# Supply_Power.net
KiCad netlist of a schematic drawn in Altium Designer
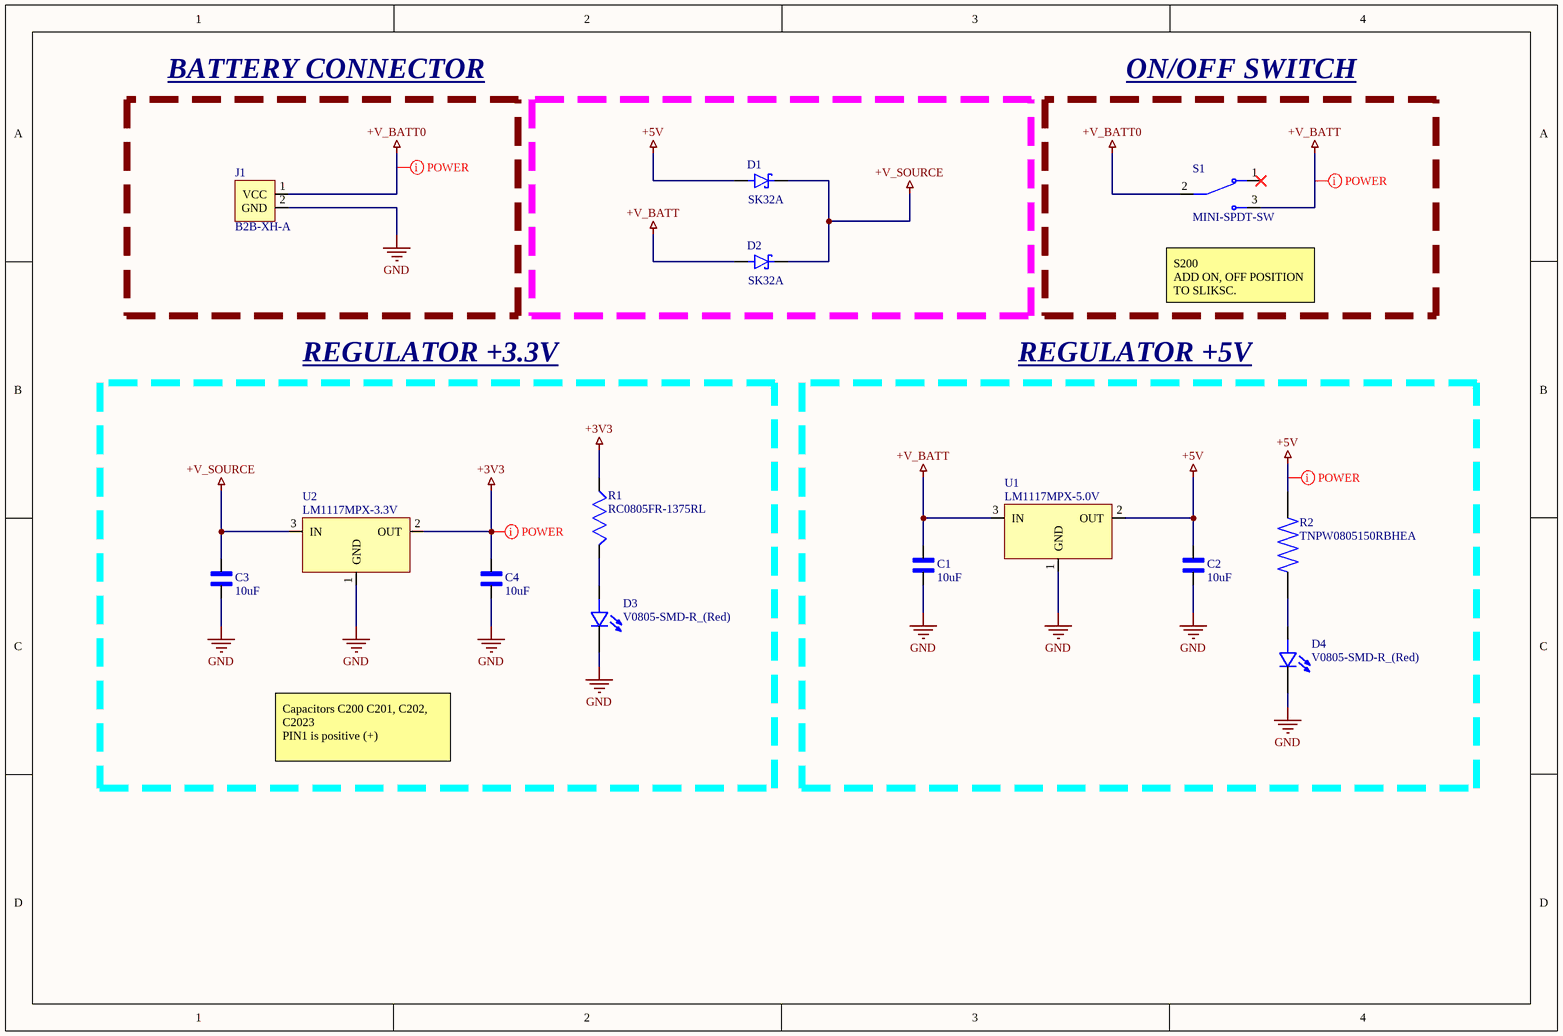
[diagram p0: Supply Power.SchDoc]

(export (version "E")
  (design (tool "Eeschema 10.0.6"))
  (components
    (comp (ref "C1")
      (value "10uF")
      (footprint "CAPPC7343X430N")
      (description "Capacitor,10uF,35VDC,10-% Tol,10+% Tol")
      (fields (field (name "MF") "{'manufacturer': u'KEMET'}") (field (name "MP") "T495D106K035AHE300"))
      (libsource (lib "Capacitor01") (part "T495D106K035AHE300"))
    )
    (comp (ref "C2")
      (value "10uF")
      (footprint "CAPPC7343X430N")
      (description "Capacitor,10uF,35VDC,10-% Tol,10+% Tol")
      (fields (field (name "MF") "{'manufacturer': u'KEMET'}") (field (name "MP") "T495D106K035AHE300"))
      (libsource (lib "Capacitor01") (part "T495D106K035AHE300"))
    )
    (comp (ref "C3")
      (value "10uF")
      (footprint "CAPPC7343X430N")
      (description "Capacitor,10uF,35VDC,10-% Tol,10+% Tol")
      (fields (field (name "MF") "{'manufacturer': u'KEMET'}") (field (name "MP") "T495D106K035AHE300"))
      (libsource (lib "Capacitor01") (part "T495D106K035AHE300"))
    )
    (comp (ref "C4")
      (value "10uF")
      (footprint "CAPPC7343X430N")
      (description "Capacitor,10uF,35VDC,10-% Tol,10+% Tol")
      (fields (field (name "MF") "{'manufacturer': u'KEMET'}") (field (name "MP") "T495D106K035AHE300"))
      (libsource (lib "Capacitor01") (part "T495D106K035AHE300"))
    )
    (comp (ref "D1")
      (value "SK32A")
      (footprint "SK32A:DIOM4325X250N")
      (fields (field (name "MF") "{'manufacturer': u'Taiwan Semiconductor'}"))
      (libsource (lib "*") (part "SK32A"))
    )
    (comp (ref "D2")
      (value "SK32A")
      (footprint "SK32A:DIOM4325X250N")
      (fields (field (name "MF") "{'manufacturer': u'Taiwan Semiconductor'}"))
      (libsource (lib "*") (part "SK32A"))
    )
    (comp (ref "D3")
      (value "V0805-SMD-R_(Red)")
      (footprint "LED_V0805-SMD-R (Red)")
      (description "V0805 - Valcon 0805 Type Surface Mount LED")
      (fields (field (name "MF") "{'manufacturer': u'Valcon'}"))
      (libsource (lib "Diode01") (part "V0805-SMD-R_(Red)"))
    )
    (comp (ref "D4")
      (value "V0805-SMD-R_(Red)")
      (footprint "LED_V0805-SMD-R (Red)")
      (description "V0805 - Valcon 0805 Type Surface Mount LED")
      (fields (field (name "MF") "{'manufacturer': u'Valcon'}"))
      (libsource (lib "Diode01") (part "V0805-SMD-R_(Red)"))
    )
    (comp (ref "J1")
      (value "B2B-XH-A")
      (footprint "B2B-XH-A")
      (libsource (lib "Sch_Library") (part "B2B-XH-A-2Pin"))
    )
    (comp (ref "R1")
      (value "RC0805FR-1375RL")
      (footprint "RESC2012X60N")
      (fields (field (name "MF") "{'manufacturer': u'Yageo'}"))
      (libsource (lib "Resistor01") (part "RC0805FR-1375RL"))
    )
    (comp (ref "R2")
      (value "TNPW0805150RBHEA")
      (footprint "RESC2012X55N")
      (fields (field (name "MF") "{'manufacturer': u'Vishay'}"))
      (libsource (lib "Resistor01") (part "TNPW0805150RBHEA"))
    )
    (comp (ref "S1")
      (value "MINI-SPDT-SW")
      (footprint "SW_MINI-SPDT-SW")
      (fields (field (name "MF") "{'manufacturer': u'Gravitech'}"))
      (libsource (lib "Button") (part "MINI-SPDT-SW"))
    )
    (comp (ref "U1")
      (value "LM1117MPX-5.0V")
      (footprint "SOT230P700X180-4N")
      (description "LM1117MPX-50NOPB")
      (libsource (lib "Sch_Library") (part "LM1117MPX-5.0V"))
    )
    (comp (ref "U2")
      (value "LM1117MPX-3.3V")
      (footprint "SOT230P700X180-4N")
      (description "LM1117MPX-33NOPB")
      (libsource (lib "Sch_Library") (part "LM1117MPX-3.3V"))
    )
  )
  (nets
    (net (code "1") (name "+3V3") (class "Default")
      (node (ref "C4") (pin "1") (pinfunction "1_1") (pintype "passive"))
      (node (ref "R1") (pin "2") (pinfunction "2_2") (pintype "passive"))
      (node (ref "U2") (pin "2") (pinfunction "OUT_2") (pintype "passive"))
    )
    (net (code "2") (name "+5V") (class "Default")
      (node (ref "C2") (pin "1") (pinfunction "1_1") (pintype "passive"))
      (node (ref "D1") (pin "A") (pinfunction "A_A") (pintype "passive"))
      (node (ref "R2") (pin "2") (pinfunction "2_2") (pintype "passive"))
      (node (ref "U1") (pin "2") (pinfunction "OUT_2") (pintype "passive"))
    )
    (net (code "3") (name "+V_BATT") (class "Default")
      (node (ref "C1") (pin "1") (pinfunction "1_1") (pintype "passive"))
      (node (ref "D2") (pin "A") (pinfunction "A_A") (pintype "passive"))
      (node (ref "S1") (pin "3") (pinfunction "3_3") (pintype "passive"))
      (node (ref "U1") (pin "3") (pinfunction "IN_3") (pintype "passive"))
    )
    (net (code "4") (name "+V_BATT0") (class "Default")
      (node (ref "J1") (pin "1") (pinfunction "VCC_1") (pintype "passive"))
      (node (ref "S1") (pin "2") (pinfunction "2_2") (pintype "passive"))
    )
    (net (code "5") (name "+V_SOURCE") (class "Default")
      (node (ref "C3") (pin "1") (pinfunction "1_1") (pintype "passive"))
      (node (ref "D1") (pin "C") (pinfunction "K_C") (pintype "passive"))
      (node (ref "D2") (pin "C") (pinfunction "K_C") (pintype "passive"))
      (node (ref "U2") (pin "3") (pinfunction "IN_3") (pintype "passive"))
    )
    (net (code "6") (name "GND") (class "Default")
      (node (ref "C1") (pin "2") (pinfunction "2_2") (pintype "passive"))
      (node (ref "C2") (pin "2") (pinfunction "2_2") (pintype "passive"))
      (node (ref "C3") (pin "2") (pinfunction "2_2") (pintype "passive"))
      (node (ref "C4") (pin "2") (pinfunction "2_2") (pintype "passive"))
      (node (ref "D3") (pin "1") (pinfunction "C_1") (pintype "passive"))
      (node (ref "D4") (pin "1") (pinfunction "C_1") (pintype "passive"))
      (node (ref "J1") (pin "2") (pinfunction "GND_2") (pintype "passive"))
      (node (ref "U1") (pin "1") (pinfunction "GND_1") (pintype "passive"))
      (node (ref "U2") (pin "1") (pinfunction "GND_1") (pintype "passive"))
    )
    (net (code "7") (name "Net-(D3-A)") (class "Default")
      (node (ref "D3") (pin "2") (pinfunction "A_2") (pintype "passive"))
      (node (ref "R1") (pin "1") (pinfunction "1_1") (pintype "passive"))
    )
    (net (code "8") (name "Net-(D4-A)") (class "Default")
      (node (ref "D4") (pin "2") (pinfunction "A_2") (pintype "passive"))
      (node (ref "R2") (pin "1") (pinfunction "1_1") (pintype "passive"))
    )
    (net (code "9") (name "unconnected-(S1-Pad1)") (class "Default")
      (node (ref "S1") (pin "1") (pinfunction "1_1") (pintype "passive+no_connect"))
    )
  )
)
